# zdrojV3.net
KiCad netlist of a schematic drawn in EAGLE
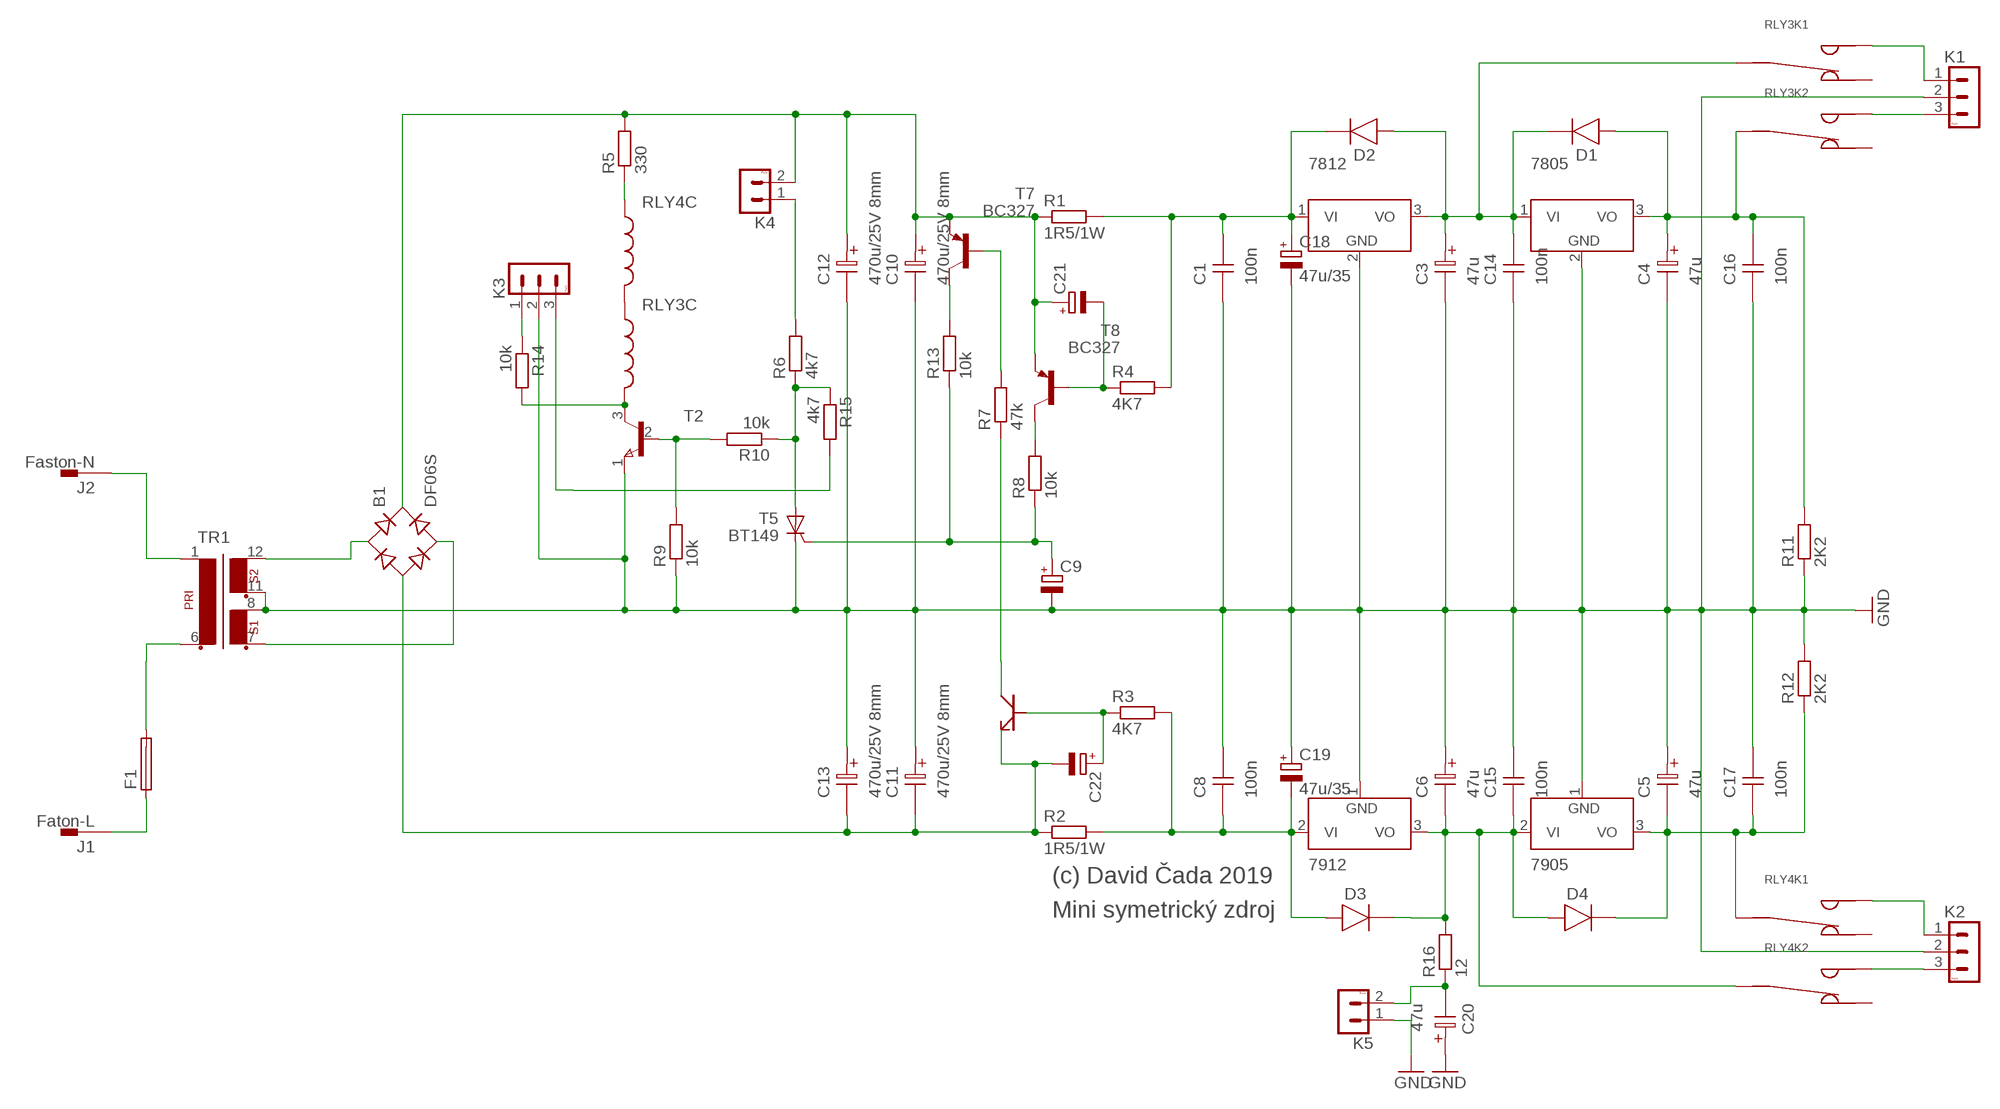
[diagram p0: schematic, sheet 1]

(export (version "E")
  (design (tool "Eeschema 10.0.6"))
  (components
    (comp (ref "7805")
      (value "7812")
      (footprint "eagle-import:TO-220S")
      (libsource (lib "eagle-import") (part "7812"))
    )
    (comp (ref "7812")
      (value "7805")
      (footprint "eagle-import:TO-220S")
      (libsource (lib "eagle-import") (part "7805"))
    )
    (comp (ref "7905")
      (value "7912")
      (footprint "eagle-import:TO-220S")
      (libsource (lib "eagle-import") (part "7912"))
    )
    (comp (ref "7912")
      (value "7905")
      (footprint "eagle-import:TO-220S")
      (libsource (lib "eagle-import") (part "7905"))
    )
    (comp (ref "B1")
      (value "DF06S")
      (footprint "eagle-import:DFS")
      (libsource (lib "eagle-import") (part "DFS06"))
    )
    (comp (ref "C1")
      (value "100n")
      (footprint "eagle-import:CK")
      (libsource (lib "eagle-import") (part "CKS"))
    )
    (comp (ref "C3")
      (value "47u")
      (footprint "eagle-import:CT12")
      (libsource (lib "eagle-import") (part "CT12"))
    )
    (comp (ref "C4")
      (value "47u")
      (footprint "eagle-import:CT12")
      (libsource (lib "eagle-import") (part "CT12"))
    )
    (comp (ref "C5")
      (value "47u")
      (footprint "eagle-import:CT12")
      (libsource (lib "eagle-import") (part "CT12"))
    )
    (comp (ref "C6")
      (value "47u")
      (footprint "eagle-import:CT12")
      (libsource (lib "eagle-import") (part "CT12"))
    )
    (comp (ref "C8")
      (value "100n")
      (footprint "eagle-import:CK")
      (libsource (lib "eagle-import") (part "CKS"))
    )
    (comp (ref "C9")
      (value "CPOL-EUE2.5-6")
      (footprint "eagle-import:E2,5-6")
      (libsource (lib "eagle-import") (part "CPOL-EUE2.5-6"))
    )
    (comp (ref "C10")
      (value "470u/25V 8mm")
      (footprint "eagle-import:CT12")
      (libsource (lib "eagle-import") (part "CT12"))
    )
    (comp (ref "C11")
      (value "470u/25V 8mm")
      (footprint "eagle-import:CT12")
      (libsource (lib "eagle-import") (part "CT12"))
    )
    (comp (ref "C12")
      (value "470u/25V 8mm")
      (footprint "eagle-import:CT12")
      (libsource (lib "eagle-import") (part "CT12"))
    )
    (comp (ref "C13")
      (value "470u/25V 8mm")
      (footprint "eagle-import:CT12")
      (libsource (lib "eagle-import") (part "CT12"))
    )
    (comp (ref "C14")
      (value "100n")
      (footprint "eagle-import:CK")
      (libsource (lib "eagle-import") (part "CKS"))
    )
    (comp (ref "C15")
      (value "100n")
      (footprint "eagle-import:CK")
      (libsource (lib "eagle-import") (part "CKS"))
    )
    (comp (ref "C16")
      (value "100n")
      (footprint "eagle-import:CK")
      (libsource (lib "eagle-import") (part "CKS"))
    )
    (comp (ref "C17")
      (value "100n")
      (footprint "eagle-import:CK")
      (libsource (lib "eagle-import") (part "CKS"))
    )
    (comp (ref "C18")
      (value "47u/35")
      (footprint "eagle-import:E2,5-6")
      (libsource (lib "eagle-import") (part "CPOL-EUE2.5-6"))
    )
    (comp (ref "C19")
      (value "47u/35")
      (footprint "eagle-import:E2,5-6")
      (libsource (lib "eagle-import") (part "CPOL-EUE2.5-6"))
    )
    (comp (ref "C20")
      (value "47u")
      (footprint "eagle-import:CT12")
      (libsource (lib "eagle-import") (part "CT12"))
    )
    (comp (ref "C21")
      (value "CPOL-EUE2.5-6")
      (footprint "eagle-import:E2,5-6")
      (libsource (lib "eagle-import") (part "CPOL-EUE2.5-6"))
    )
    (comp (ref "C22")
      (value "CPOL-EUE2.5-6")
      (footprint "eagle-import:E2,5-6")
      (libsource (lib "eagle-import") (part "CPOL-EUE2.5-6"))
    )
    (comp (ref "D1")
      (value "1N4007")
      (footprint "eagle-import:DO41")
      (libsource (lib "eagle-import") (part "1N4007"))
    )
    (comp (ref "D2")
      (value "1N4007")
      (footprint "eagle-import:DO41")
      (libsource (lib "eagle-import") (part "1N4007"))
    )
    (comp (ref "D3")
      (value "1N4007")
      (footprint "eagle-import:DO41")
      (libsource (lib "eagle-import") (part "1N4007"))
    )
    (comp (ref "D4")
      (value "1N4007")
      (footprint "eagle-import:DO41")
      (libsource (lib "eagle-import") (part "1N4007"))
    )
    (comp (ref "F1")
      (value "19560")
      (footprint "eagle-import:19560")
      (fields (field (name "MPN") "56000001009"))
      (libsource (lib "eagle-import") (part "19560"))
    )
    (comp (ref "J1")
      (value "Faton-L")
      (footprint "eagle-import:F061.100")
      (libsource (lib "eagle-import") (part "PIN2F061.100"))
    )
    (comp (ref "J2")
      (value "Faston-N")
      (footprint "eagle-import:F061.100")
      (libsource (lib "eagle-import") (part "PIN2F061.100"))
    )
    (comp (ref "K1")
      (value "PSH02-03P")
      (footprint "eagle-import:PSH02-03P")
      (libsource (lib "eagle-import") (part "PSH02-03P"))
    )
    (comp (ref "K2")
      (value "PSH02-03P")
      (footprint "eagle-import:PSH02-03P")
      (libsource (lib "eagle-import") (part "PSH02-03P"))
    )
    (comp (ref "K3")
      (value "PSH02-03P")
      (footprint "eagle-import:PSH02-03P")
      (libsource (lib "eagle-import") (part "PSH02-03P"))
    )
    (comp (ref "K4")
      (value "PSH02-02P")
      (footprint "eagle-import:PSH02-02P")
      (libsource (lib "eagle-import") (part "PSH02-02P"))
    )
    (comp (ref "K5")
      (value "PSH02-02P")
      (footprint "eagle-import:PSH02-02P")
      (libsource (lib "eagle-import") (part "PSH02-02P"))
    )
    (comp (ref "R1")
      (value "1R5/1W")
      (footprint "eagle-import:0411V")
      (libsource (lib "eagle-import") (part "R-EU_0411/3V"))
    )
    (comp (ref "R2")
      (value "1R5/1W")
      (footprint "eagle-import:0411V")
      (libsource (lib "eagle-import") (part "R-EU_0411/3V"))
    )
    (comp (ref "R3")
      (value "4K7")
      (footprint "eagle-import:0207_2V")
      (libsource (lib "eagle-import") (part "R-EU_0207/2V"))
    )
    (comp (ref "R4")
      (value "4K7")
      (footprint "eagle-import:0207_2V")
      (libsource (lib "eagle-import") (part "R-EU_0207/2V"))
    )
    (comp (ref "R5")
      (value "330")
      (footprint "eagle-import:0207_2V")
      (libsource (lib "eagle-import") (part "R-EU_0207/2V"))
    )
    (comp (ref "R6")
      (value "4k7")
      (footprint "eagle-import:0207_2V")
      (libsource (lib "eagle-import") (part "R-EU_0207/2V"))
    )
    (comp (ref "R7")
      (value "47k")
      (footprint "eagle-import:0207_2V")
      (libsource (lib "eagle-import") (part "R-EU_0207/2V"))
    )
    (comp (ref "R8")
      (value "10k")
      (footprint "eagle-import:0207_2V")
      (libsource (lib "eagle-import") (part "R-EU_0207/2V"))
    )
    (comp (ref "R9")
      (value "10k")
      (footprint "eagle-import:0207_2V")
      (libsource (lib "eagle-import") (part "R-EU_0207/2V"))
    )
    (comp (ref "R10")
      (value "10k")
      (footprint "eagle-import:0207_2V")
      (libsource (lib "eagle-import") (part "R-EU_0207/2V"))
    )
    (comp (ref "R11")
      (value "2K2")
      (footprint "eagle-import:0207_2V")
      (libsource (lib "eagle-import") (part "R-EU_0207/2V"))
    )
    (comp (ref "R12")
      (value "2K2")
      (footprint "eagle-import:0207_2V")
      (libsource (lib "eagle-import") (part "R-EU_0207/2V"))
    )
    (comp (ref "R13")
      (value "10k")
      (footprint "eagle-import:0207_2V")
      (libsource (lib "eagle-import") (part "R-EU_0207/2V"))
    )
    (comp (ref "R14")
      (value "10k")
      (footprint "eagle-import:0207_2V")
      (libsource (lib "eagle-import") (part "R-EU_0207/2V"))
    )
    (comp (ref "R15")
      (value "4k7")
      (footprint "eagle-import:0207_2V")
      (libsource (lib "eagle-import") (part "R-EU_0207/2V"))
    )
    (comp (ref "R16")
      (value "12")
      (footprint "eagle-import:0207_2V")
      (libsource (lib "eagle-import") (part "R-EU_0207/2V"))
    )
    (comp (ref "RLY3")
      (value "RELEG5V2")
      (footprint "eagle-import:RG5V2")
      (libsource (lib "eagle-import") (part "RELEG5V2"))
    )
    (comp (ref "RLY4")
      (value "RELEG5V2")
      (footprint "eagle-import:RG5V2")
      (libsource (lib "eagle-import") (part "RELEG5V2"))
    )
    (comp (ref "T2")
      (value "BC337-40")
      (footprint "eagle-import:TO-92C")
      (libsource (lib "eagle-import") (part "BC337-40"))
    )
    (comp (ref "T5")
      (value "BT149")
      (footprint "eagle-import:TO92-4")
      (libsource (lib "eagle-import") (part "BT149"))
    )
    (comp (ref "T6")
      (value "MPSA44")
      (footprint "eagle-import:TO92-EBC")
      (libsource (lib "eagle-import") (part "MPSA44"))
    )
    (comp (ref "T7")
      (value "BC327")
      (footprint "eagle-import:TO92")
      (libsource (lib "eagle-import") (part "BC327"))
    )
    (comp (ref "T8")
      (value "BC327")
      (footprint "eagle-import:TO92")
      (libsource (lib "eagle-import") (part "BC327"))
    )
    (comp (ref "TR1")
      (value "EI48-2")
      (footprint "eagle-import:EI48-2")
      (libsource (lib "eagle-import") (part "EI48-2"))
    )
  )
  (nets
    (net (code "1") (name "GND") (class "Default")
      (node (ref "7805") (pin "2") (pinfunction "GND_2") (pintype "input"))
      (node (ref "7812") (pin "2") (pinfunction "GND_2") (pintype "input"))
      (node (ref "7905") (pin "1") (pinfunction "GND_1") (pintype "input"))
      (node (ref "7912") (pin "1") (pinfunction "GND_1") (pintype "input"))
      (node (ref "C1") (pin "1") (pinfunction "1_1") (pintype "passive"))
      (node (ref "C10") (pin "2") (pinfunction "2_2") (pintype "passive"))
      (node (ref "C11") (pin "1") (pinfunction "1_1") (pintype "passive"))
      (node (ref "C12") (pin "2") (pinfunction "2_2") (pintype "passive"))
      (node (ref "C13") (pin "1") (pinfunction "1_1") (pintype "passive"))
      (node (ref "C14") (pin "1") (pinfunction "1_1") (pintype "passive"))
      (node (ref "C15") (pin "2") (pinfunction "2_2") (pintype "passive"))
      (node (ref "C16") (pin "1") (pinfunction "1_1") (pintype "passive"))
      (node (ref "C17") (pin "2") (pinfunction "2_2") (pintype "passive"))
      (node (ref "C18") (pin "-") (pinfunction "-_-") (pintype "passive"))
      (node (ref "C19") (pin "+") (pinfunction "+_+") (pintype "passive"))
      (node (ref "C20") (pin "1") (pinfunction "1_1") (pintype "passive"))
      (node (ref "C3") (pin "2") (pinfunction "2_2") (pintype "passive"))
      (node (ref "C4") (pin "2") (pinfunction "2_2") (pintype "passive"))
      (node (ref "C5") (pin "1") (pinfunction "1_1") (pintype "passive"))
      (node (ref "C6") (pin "1") (pinfunction "1_1") (pintype "passive"))
      (node (ref "C8") (pin "2") (pinfunction "2_2") (pintype "passive"))
      (node (ref "C9") (pin "-") (pinfunction "-_-") (pintype "passive"))
      (node (ref "K1") (pin "2") (pinfunction "2_2") (pintype "passive"))
      (node (ref "K2") (pin "2") (pinfunction "2_2") (pintype "passive"))
      (node (ref "K3") (pin "2") (pinfunction "2_2") (pintype "passive"))
      (node (ref "K5") (pin "1") (pinfunction "1_1") (pintype "passive"))
      (node (ref "R11") (pin "1") (pinfunction "1_1") (pintype "passive"))
      (node (ref "R12") (pin "2") (pinfunction "2_2") (pintype "passive"))
      (node (ref "R9") (pin "1") (pinfunction "1_1") (pintype "passive"))
      (node (ref "T2") (pin "1") (pinfunction "E_1") (pintype "passive"))
      (node (ref "T5") (pin "C") (pinfunction "C_C") (pintype "passive"))
      (node (ref "TR1") (pin "11") (pinfunction "5_11") (pintype "passive"))
      (node (ref "TR1") (pin "8") (pinfunction "4_8") (pintype "passive"))
    )
    (net (code "2") (name "Net-(7805-VI)") (class "Default")
      (node (ref "7805") (pin "1") (pinfunction "VI_1") (pintype "input"))
      (node (ref "7812") (pin "3") (pinfunction "VO_3") (pintype "output"))
      (node (ref "C14") (pin "2") (pinfunction "2_2") (pintype "passive"))
      (node (ref "C3") (pin "1") (pinfunction "1_1") (pintype "passive"))
      (node (ref "D1") (pin "K") (pinfunction "K_K") (pintype "passive"))
      (node (ref "D2") (pin "A") (pinfunction "A_A") (pintype "passive"))
      (node (ref "RLY3") (pin "3") (pinfunction "3_3") (pintype "passive"))
    )
    (net (code "3") (name "Net-(7805-VO)") (class "Default")
      (node (ref "7805") (pin "3") (pinfunction "VO_3") (pintype "output"))
      (node (ref "C16") (pin "2") (pinfunction "2_2") (pintype "passive"))
      (node (ref "C4") (pin "1") (pinfunction "1_1") (pintype "passive"))
      (node (ref "D1") (pin "A") (pinfunction "A_A") (pintype "passive"))
      (node (ref "R11") (pin "2") (pinfunction "2_2") (pintype "passive"))
      (node (ref "RLY3") (pin "6") (pinfunction "3_6") (pintype "passive"))
    )
    (net (code "4") (name "Net-(7812-VI)") (class "Default")
      (node (ref "7812") (pin "1") (pinfunction "VI_1") (pintype "input"))
      (node (ref "C1") (pin "2") (pinfunction "2_2") (pintype "passive"))
      (node (ref "C18") (pin "+") (pinfunction "+_+") (pintype "passive"))
      (node (ref "D2") (pin "K") (pinfunction "K_K") (pintype "passive"))
      (node (ref "R1") (pin "2") (pinfunction "2_2") (pintype "passive"))
      (node (ref "R4") (pin "2") (pinfunction "2_2") (pintype "passive"))
    )
    (net (code "5") (name "Net-(7905-VI)") (class "Default")
      (node (ref "7905") (pin "2") (pinfunction "VI_2") (pintype "input"))
      (node (ref "7912") (pin "3") (pinfunction "VO_3") (pintype "output"))
      (node (ref "C15") (pin "1") (pinfunction "1_1") (pintype "passive"))
      (node (ref "C6") (pin "2") (pinfunction "2_2") (pintype "passive"))
      (node (ref "D3") (pin "K") (pinfunction "K_K") (pintype "passive"))
      (node (ref "D4") (pin "A") (pinfunction "A_A") (pintype "passive"))
      (node (ref "R16") (pin "2") (pinfunction "2_2") (pintype "passive"))
      (node (ref "RLY4") (pin "6") (pinfunction "3_6") (pintype "passive"))
    )
    (net (code "6") (name "Net-(7905-VO)") (class "Default")
      (node (ref "7905") (pin "3") (pinfunction "VO_3") (pintype "output"))
      (node (ref "C17") (pin "1") (pinfunction "1_1") (pintype "passive"))
      (node (ref "C5") (pin "2") (pinfunction "2_2") (pintype "passive"))
      (node (ref "D4") (pin "K") (pinfunction "K_K") (pintype "passive"))
      (node (ref "R12") (pin "1") (pinfunction "1_1") (pintype "passive"))
      (node (ref "RLY4") (pin "3") (pinfunction "3_3") (pintype "passive"))
    )
    (net (code "7") (name "Net-(7912-VI)") (class "Default")
      (node (ref "7912") (pin "2") (pinfunction "VI_2") (pintype "input"))
      (node (ref "C19") (pin "-") (pinfunction "-_-") (pintype "passive"))
      (node (ref "C8") (pin "1") (pinfunction "1_1") (pintype "passive"))
      (node (ref "D3") (pin "A") (pinfunction "A_A") (pintype "passive"))
      (node (ref "R2") (pin "2") (pinfunction "2_2") (pintype "passive"))
      (node (ref "R3") (pin "2") (pinfunction "2_2") (pintype "passive"))
    )
    (net (code "8") (name "Net-(C9-Pad+)") (class "Default")
      (node (ref "C9") (pin "+") (pinfunction "+_+") (pintype "passive"))
      (node (ref "R13") (pin "1") (pinfunction "1_1") (pintype "passive"))
      (node (ref "R8") (pin "1") (pinfunction "1_1") (pintype "passive"))
      (node (ref "T5") (pin "G") (pinfunction "G_G") (pintype "passive"))
    )
    (net (code "9") (name "Net-(C20-Pad2)") (class "Default")
      (node (ref "C20") (pin "2") (pinfunction "2_2") (pintype "passive"))
      (node (ref "K5") (pin "2") (pinfunction "2_2") (pintype "passive"))
      (node (ref "R16") (pin "1") (pinfunction "1_1") (pintype "passive"))
    )
    (net (code "10") (name "Net-(C22-Pad+)") (class "Default")
      (node (ref "C22") (pin "+") (pinfunction "+_+") (pintype "passive"))
      (node (ref "R3") (pin "1") (pinfunction "1_1") (pintype "passive"))
      (node (ref "T6") (pin "B") (pinfunction "B_B") (pintype "bidirectional"))
    )
    (net (code "11") (name "Net-(F1-Pad1)") (class "Default")
      (node (ref "F1") (pin "1") (pinfunction "1_1") (pintype "passive"))
      (node (ref "J1") (pin "A1") (pinfunction "1_A1") (pintype "passive"))
      (node (ref "J1") (pin "A2") (pinfunction "1_A2") (pintype "passive"))
    )
    (net (code "12") (name "Net-(J2-1-PadA1)") (class "Default")
      (node (ref "J2") (pin "A1") (pinfunction "1_A1") (pintype "passive"))
      (node (ref "J2") (pin "A2") (pinfunction "1_A2") (pintype "passive"))
      (node (ref "TR1") (pin "1") (pinfunction "1_1") (pintype "passive"))
    )
    (net (code "13") (name "Net-(K3-Pad1)") (class "Default")
      (node (ref "K3") (pin "1") (pinfunction "1_1") (pintype "passive"))
      (node (ref "R14") (pin "1") (pinfunction "1_1") (pintype "passive"))
    )
    (net (code "14") (name "Net-(K3-Pad3)") (class "Default")
      (node (ref "K3") (pin "3") (pinfunction "3_3") (pintype "passive"))
      (node (ref "R15") (pin "2") (pinfunction "2_2") (pintype "passive"))
    )
    (net (code "15") (name "Net-(K4-Pad1)") (class "Default")
      (node (ref "K4") (pin "1") (pinfunction "1_1") (pintype "passive"))
      (node (ref "R6") (pin "2") (pinfunction "2_2") (pintype "passive"))
    )
    (net (code "16") (name "Net-(R5-Pad1)") (class "Default")
      (node (ref "R5") (pin "1") (pinfunction "1_1") (pintype "passive"))
      (node (ref "RLY4") (pin "1") (pinfunction "1_1") (pintype "passive"))
    )
    (net (code "17") (name "Net-(R10-Pad1)") (class "Default")
      (node (ref "R10") (pin "1") (pinfunction "1_1") (pintype "passive"))
      (node (ref "R15") (pin "1") (pinfunction "1_1") (pintype "passive"))
      (node (ref "R6") (pin "1") (pinfunction "1_1") (pintype "passive"))
      (node (ref "T5") (pin "A") (pinfunction "A_A") (pintype "passive"))
    )
    (net (code "18") (name "Net-(RLY3-Pad1)") (class "Default")
      (node (ref "RLY3") (pin "1") (pinfunction "1_1") (pintype "passive"))
      (node (ref "RLY4") (pin "2") (pinfunction "2_2") (pintype "passive"))
    )
    (net (code "19") (name "Net-(RLY3B-1)") (class "Default")
      (node (ref "K1") (pin "1") (pinfunction "1_1") (pintype "passive"))
      (node (ref "RLY3") (pin "5") (pinfunction "1_5") (pintype "passive"))
    )
    (net (code "20") (name "Net-(RLY3C-1)") (class "Default")
      (node (ref "K1") (pin "3") (pinfunction "3_3") (pintype "passive"))
      (node (ref "RLY3") (pin "8") (pinfunction "1_8") (pintype "passive"))
    )
    (net (code "21") (name "Net-(RLY4B-1)") (class "Default")
      (node (ref "K2") (pin "1") (pinfunction "1_1") (pintype "passive"))
      (node (ref "RLY4") (pin "5") (pinfunction "1_5") (pintype "passive"))
    )
    (net (code "22") (name "Net-(RLY4C-1)") (class "Default")
      (node (ref "K2") (pin "3") (pinfunction "3_3") (pintype "passive"))
      (node (ref "RLY4") (pin "8") (pinfunction "1_8") (pintype "passive"))
    )
    (net (code "23") (name "Net-(T2-B)") (class "Default")
      (node (ref "R10") (pin "2") (pinfunction "2_2") (pintype "passive"))
      (node (ref "R9") (pin "2") (pinfunction "2_2") (pintype "passive"))
      (node (ref "T2") (pin "2") (pinfunction "B_2") (pintype "passive"))
    )
    (net (code "24") (name "Net-(T2-C)") (class "Default")
      (node (ref "R14") (pin "2") (pinfunction "2_2") (pintype "passive"))
      (node (ref "RLY3") (pin "2") (pinfunction "2_2") (pintype "passive"))
      (node (ref "T2") (pin "3") (pinfunction "C_3") (pintype "passive"))
    )
    (net (code "25") (name "Net-(T6-C)") (class "Default")
      (node (ref "R7") (pin "1") (pinfunction "1_1") (pintype "passive"))
      (node (ref "T6") (pin "E") (pinfunction "C_E") (pintype "bidirectional"))
    )
    (net (code "26") (name "Net-(T6-E)") (class "Default")
      (node (ref "B1") (pin "-") (pinfunction "-_-") (pintype "passive"))
      (node (ref "C11") (pin "2") (pinfunction "2_2") (pintype "passive"))
      (node (ref "C13") (pin "2") (pinfunction "2_2") (pintype "passive"))
      (node (ref "C22") (pin "-") (pinfunction "-_-") (pintype "passive"))
      (node (ref "R2") (pin "1") (pinfunction "1_1") (pintype "passive"))
      (node (ref "T6") (pin "C") (pinfunction "E_C") (pintype "bidirectional"))
    )
    (net (code "27") (name "Net-(T7-B)") (class "Default")
      (node (ref "R7") (pin "2") (pinfunction "2_2") (pintype "passive"))
      (node (ref "T7") (pin "2") (pinfunction "B_2") (pintype "passive"))
    )
    (net (code "28") (name "Net-(T7-C)") (class "Default")
      (node (ref "R13") (pin "2") (pinfunction "2_2") (pintype "passive"))
      (node (ref "T7") (pin "3") (pinfunction "C_3") (pintype "passive"))
    )
    (net (code "29") (name "Net-(T7-E)") (class "Default")
      (node (ref "B1") (pin "+") (pinfunction "+_+") (pintype "passive"))
      (node (ref "C10") (pin "1") (pinfunction "1_1") (pintype "passive"))
      (node (ref "C12") (pin "1") (pinfunction "1_1") (pintype "passive"))
      (node (ref "C21") (pin "+") (pinfunction "+_+") (pintype "passive"))
      (node (ref "K4") (pin "2") (pinfunction "2_2") (pintype "passive"))
      (node (ref "R1") (pin "1") (pinfunction "1_1") (pintype "passive"))
      (node (ref "R5") (pin "2") (pinfunction "2_2") (pintype "passive"))
      (node (ref "T7") (pin "1") (pinfunction "E_1") (pintype "passive"))
      (node (ref "T8") (pin "1") (pinfunction "E_1") (pintype "passive"))
    )
    (net (code "30") (name "Net-(T8-B)") (class "Default")
      (node (ref "C21") (pin "-") (pinfunction "-_-") (pintype "passive"))
      (node (ref "R4") (pin "1") (pinfunction "1_1") (pintype "passive"))
      (node (ref "T8") (pin "2") (pinfunction "B_2") (pintype "passive"))
    )
    (net (code "31") (name "Net-(T8-C)") (class "Default")
      (node (ref "R8") (pin "2") (pinfunction "2_2") (pintype "passive"))
      (node (ref "T8") (pin "3") (pinfunction "C_3") (pintype "passive"))
    )
    (net (code "32") (name "Net-(TR1-2)") (class "Default")
      (node (ref "F1") (pin "2") (pinfunction "2_2") (pintype "passive"))
      (node (ref "TR1") (pin "6") (pinfunction "2_6") (pintype "passive"))
    )
    (net (code "33") (name "Net-(TR1-3)") (class "Default")
      (node (ref "B1") (pin "AC2") (pinfunction "AC2_AC2") (pintype "passive"))
      (node (ref "TR1") (pin "7") (pinfunction "3_7") (pintype "passive"))
    )
    (net (code "34") (name "Net-(TR1-6)") (class "Default")
      (node (ref "B1") (pin "AC1") (pinfunction "AC1_AC1") (pintype "passive"))
      (node (ref "TR1") (pin "12") (pinfunction "6_12") (pintype "passive"))
    )
    (net (code "35") (name "unconnected-(RLY3B-2-Pad4)") (class "Default")
      (node (ref "RLY3") (pin "4") (pinfunction "2_4") (pintype "passive"))
    )
    (net (code "36") (name "unconnected-(RLY3C-2-Pad7)") (class "Default")
      (node (ref "RLY3") (pin "7") (pinfunction "2_7") (pintype "passive"))
    )
    (net (code "37") (name "unconnected-(RLY4B-2-Pad4)") (class "Default")
      (node (ref "RLY4") (pin "4") (pinfunction "2_4") (pintype "passive"))
    )
    (net (code "38") (name "unconnected-(RLY4C-2-Pad7)") (class "Default")
      (node (ref "RLY4") (pin "7") (pinfunction "2_7") (pintype "passive"))
    )
  )
)
